# design.net
KiCad netlist of a schematic drawn in Altium Designer
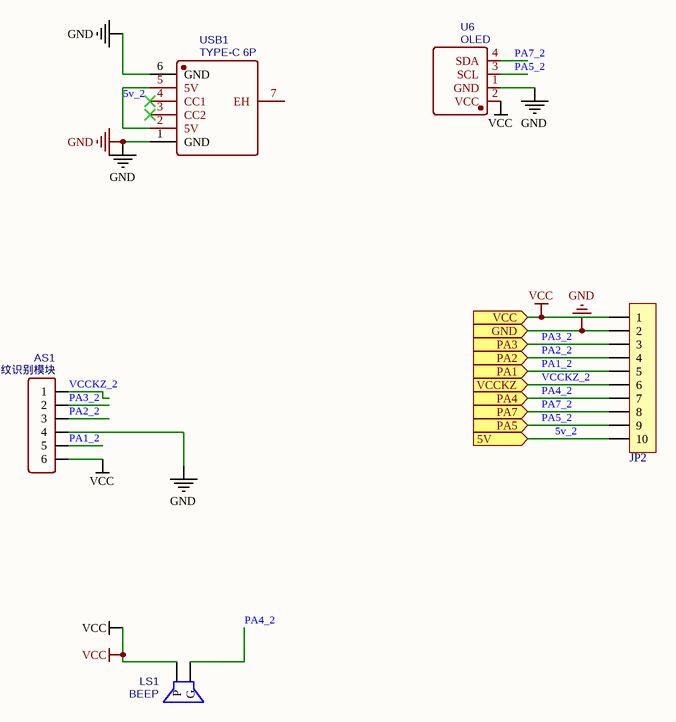
[diagram p0: 控制.SchDoc]

(export (version "E")
  (design (tool "Eeschema 10.0.6"))
  (components
    (comp (ref "AS1")
      (value "指纹识别模块")
      (footprint "HDR2.54-WI-6P")
      (fields (field (name "BOM_SUPPLIER PART") "C190819") (field (name "CONTRIBUTOR") "LCEDA_Lib"))
      (libsource (lib "altium-import") (part "root_0_指纹识别模块_"))
    )
    (comp (ref "JP2")
      (value "HDR-1X10")
      (footprint "MX 1.25-WI-10P")
      (description "10P接插件")
      (libsource (lib "5.0 - 接插件-脚距1.25") (part "Header 10"))
    )
    (comp (ref "LS1")
      (value "BEEP")
      (footprint "BEEP 6.5x12x6")
      (fields (field (name "CONTRIBUTOR") "nibo"))
      (libsource (lib "altium-import") (part "root_3_BEEP_"))
    )
    (comp (ref "U6")
      (value "OLED")
      (footprint "0.96_OLED")
      (fields (field (name "CONTRIBUTOR") "Sheikah"))
      (libsource (lib "altium-import") (part "root_2_OLED_"))
    )
    (comp (ref "USB1")
      (value "TYPE-C 6P")
      (footprint "USB-C-SMD_10P-P1.00-L6.8-W8.9")
      (fields (field (name "BOM_SUPPLIER PART") "C456012") (field (name "CONTRIBUTOR") "youzige"))
      (libsource (lib "altium-import") (part "root_0_TYPE-C 6P_"))
    )
  )
  (nets
    (net (code "1") (name "/5v_2") (class "Default")
      (node (ref "JP2") (pin "10") (pinfunction "10_10") (pintype "passive"))
      (node (ref "USB1") (pin "2") (pinfunction "5V_2") (pintype "passive"))
      (node (ref "USB1") (pin "5") (pinfunction "5V_5") (pintype "passive"))
    )
    (net (code "2") (name "/PA1_2") (class "Default")
      (node (ref "AS1") (pin "5") (pinfunction "5_5") (pintype "passive"))
      (node (ref "JP2") (pin "5") (pinfunction "5_5") (pintype "passive"))
    )
    (net (code "3") (name "/PA2_2") (class "Default")
      (node (ref "AS1") (pin "3") (pinfunction "3_3") (pintype "passive"))
      (node (ref "JP2") (pin "4") (pinfunction "4_4") (pintype "passive"))
    )
    (net (code "4") (name "/PA3_2") (class "Default")
      (node (ref "AS1") (pin "2") (pinfunction "2_2") (pintype "passive"))
      (node (ref "JP2") (pin "3") (pinfunction "3_3") (pintype "passive"))
    )
    (net (code "5") (name "/PA4_2") (class "Default")
      (node (ref "JP2") (pin "7") (pinfunction "7_7") (pintype "passive"))
      (node (ref "LS1") (pin "2") (pinfunction "G_2") (pintype "passive"))
    )
    (net (code "6") (name "/PA5_2") (class "Default")
      (node (ref "JP2") (pin "9") (pinfunction "9_9") (pintype "passive"))
      (node (ref "U6") (pin "3") (pinfunction "SCL_3") (pintype "passive"))
    )
    (net (code "7") (name "/PA7_2") (class "Default")
      (node (ref "JP2") (pin "8") (pinfunction "8_8") (pintype "passive"))
      (node (ref "U6") (pin "4") (pinfunction "SDA_4") (pintype "passive"))
    )
    (net (code "8") (name "/VCCKZ_2") (class "Default")
      (node (ref "AS1") (pin "1") (pinfunction "1_1") (pintype "passive"))
      (node (ref "JP2") (pin "6") (pinfunction "6_6") (pintype "passive"))
    )
    (net (code "9") (name "GND") (class "Default")
      (node (ref "AS1") (pin "4") (pinfunction "4_4") (pintype "passive"))
      (node (ref "JP2") (pin "2") (pinfunction "2_2") (pintype "passive"))
      (node (ref "U6") (pin "1") (pinfunction "GND_1") (pintype "passive"))
      (node (ref "USB1") (pin "1") (pinfunction "GND_1") (pintype "passive"))
      (node (ref "USB1") (pin "6") (pinfunction "GND_6") (pintype "passive"))
    )
    (net (code "10") (name "VCC") (class "Default")
      (node (ref "AS1") (pin "6") (pinfunction "6_6") (pintype "passive"))
      (node (ref "JP2") (pin "1") (pinfunction "1_1") (pintype "passive"))
      (node (ref "LS1") (pin "1") (pinfunction "P_1") (pintype "passive"))
      (node (ref "U6") (pin "2") (pinfunction "VCC_2") (pintype "passive"))
    )
    (net (code "11") (name "unconnected-(USB1-CC1-Pad4)") (class "Default")
      (node (ref "USB1") (pin "4") (pinfunction "CC1_4") (pintype "passive+no_connect"))
    )
    (net (code "12") (name "unconnected-(USB1-CC2-Pad3)") (class "Default")
      (node (ref "USB1") (pin "3") (pinfunction "CC2_3") (pintype "passive+no_connect"))
    )
    (net (code "13") (name "unconnected-(USB1-EH-Pad7)") (class "Default")
      (node (ref "USB1") (pin "7") (pinfunction "EH_7") (pintype "passive"))
    )
  )
)
